# TT7-F_v1_4.net
KiCad netlist of a schematic drawn in EAGLE
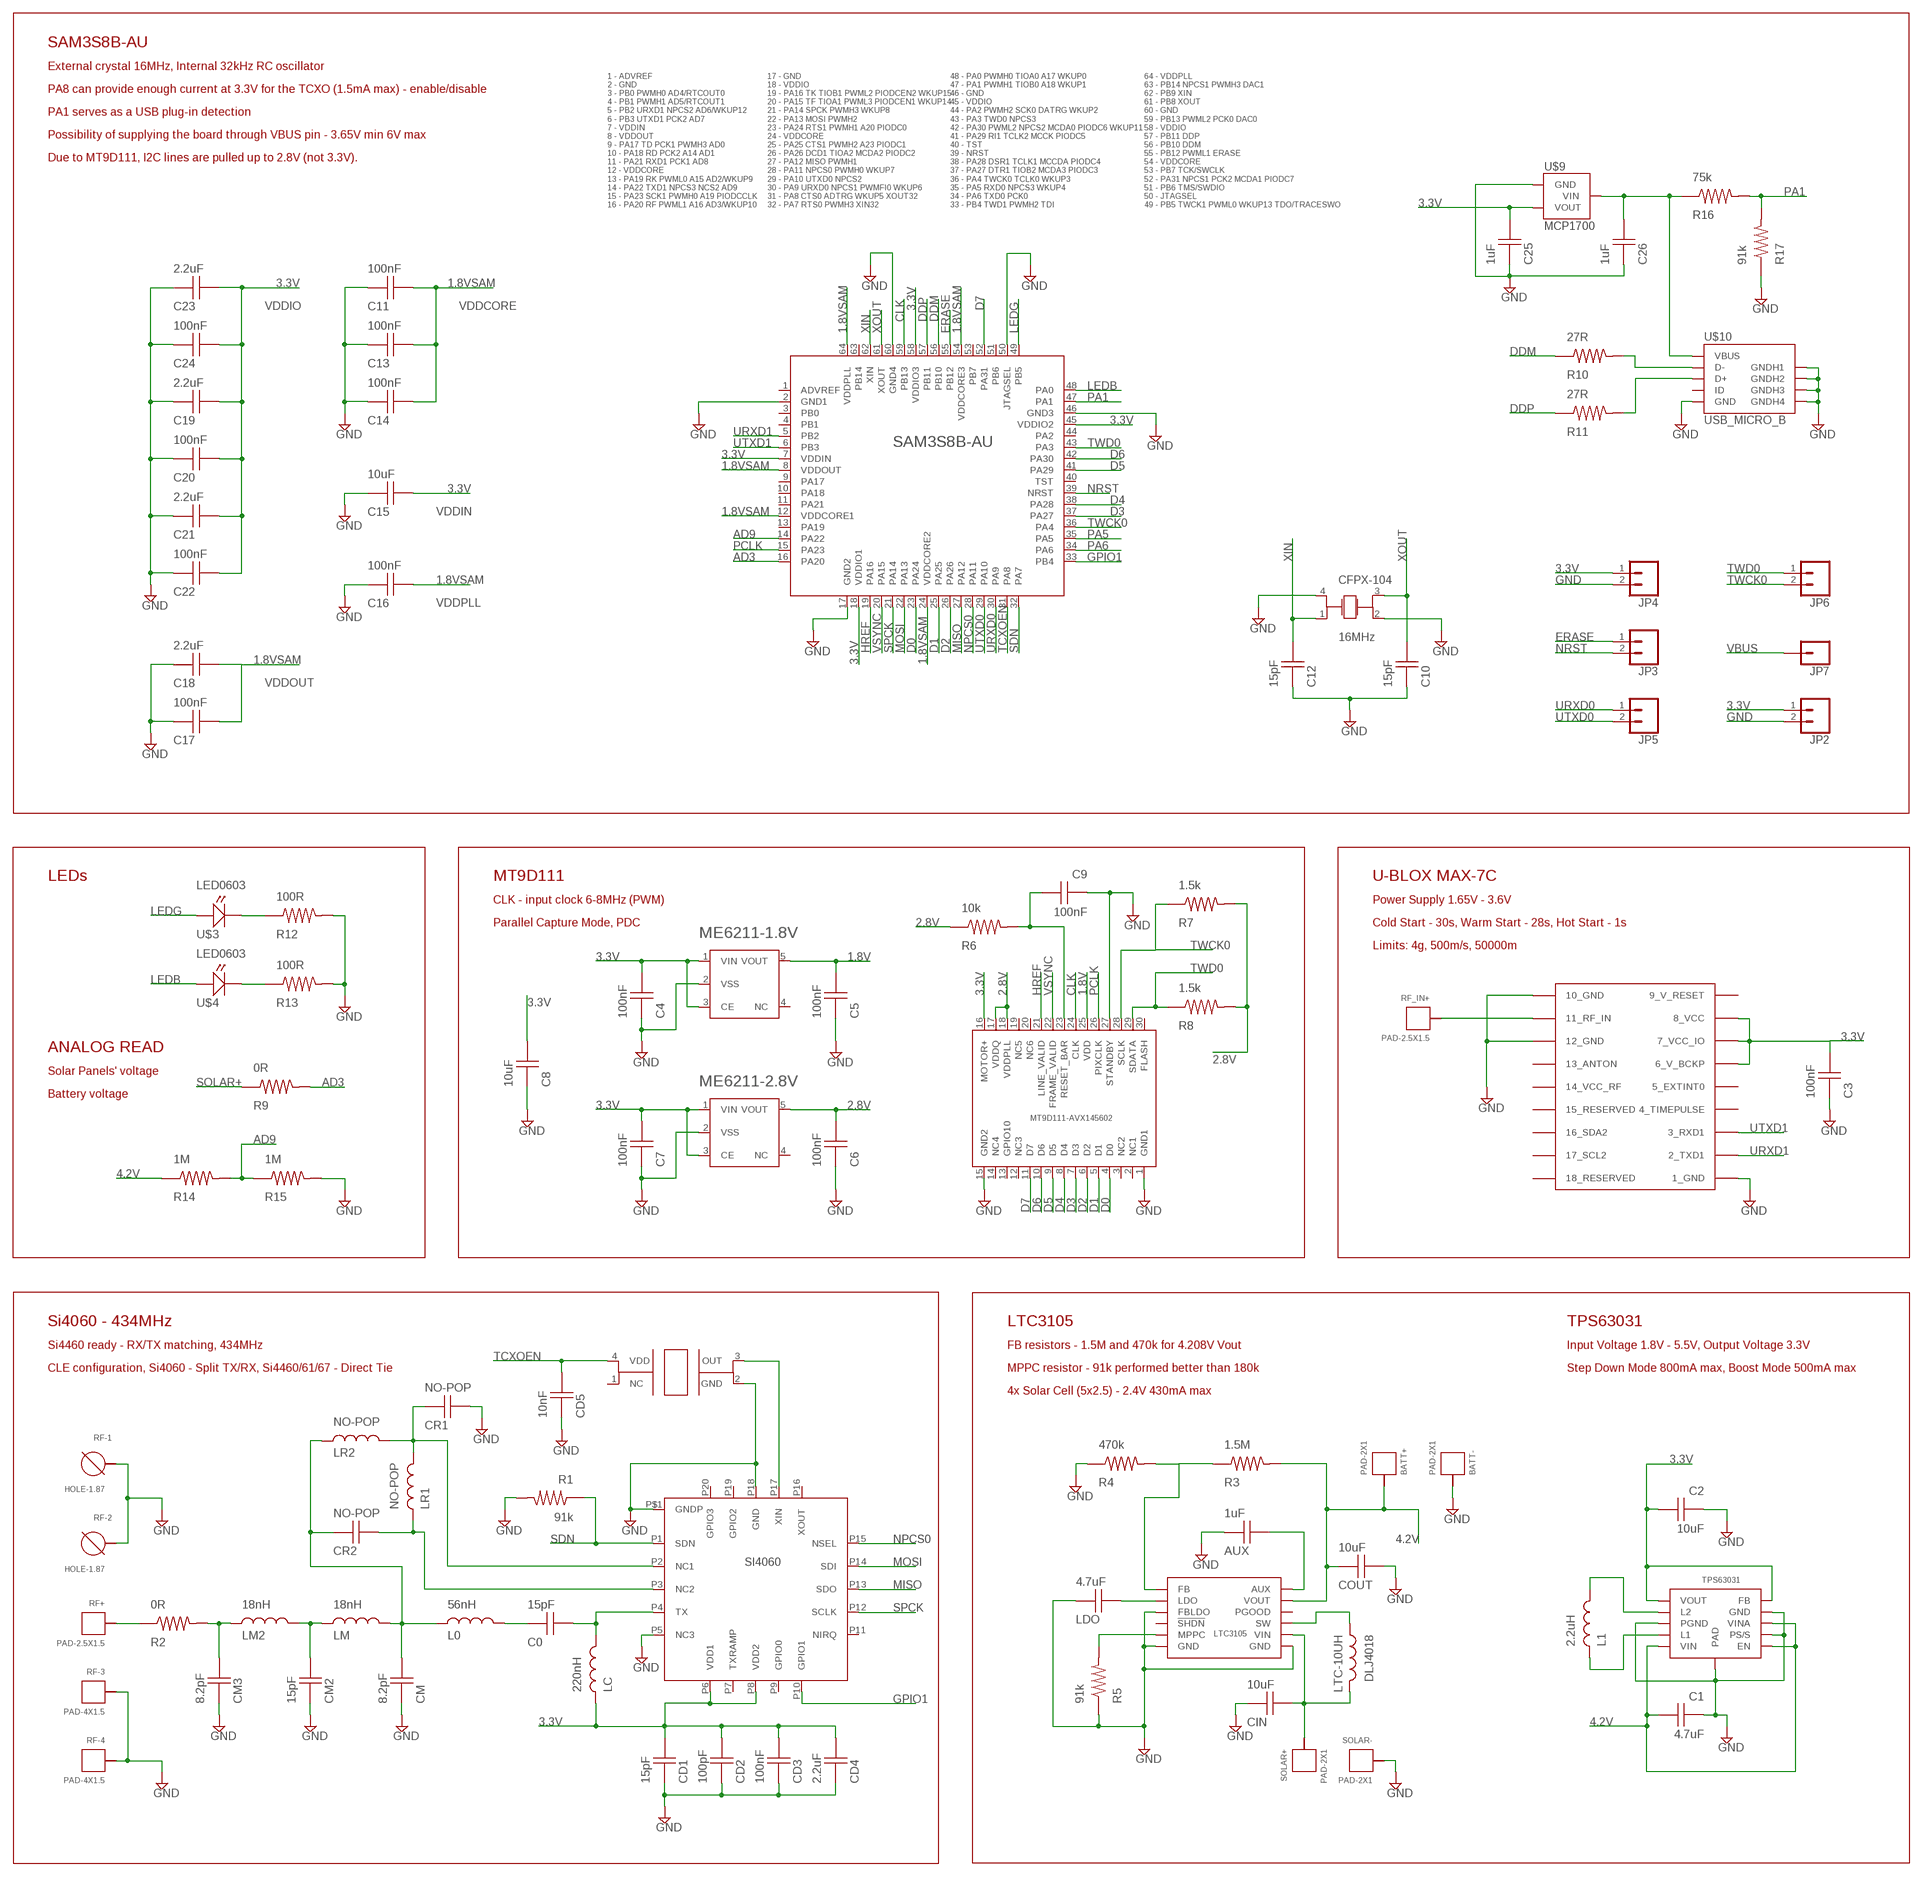
[diagram p0: schematic, sheet 1]

(export (version "E")
  (design (tool "Eeschema 10.0.6"))
  (components
    (comp (ref "AUX")
      (value "1uF")
      (footprint "eagle-import:CAP0603")
      (libsource (lib "eagle-import") (part "CAP0603"))
    )
    (comp (ref "BATT+")
      (value "PAD-2X1")
      (footprint "eagle-import:PAD-2X1")
      (libsource (lib "eagle-import") (part "PAD-2X1"))
    )
    (comp (ref "BATT-")
      (value "PAD-2X1")
      (footprint "eagle-import:PAD-2X1")
      (libsource (lib "eagle-import") (part "PAD-2X1"))
    )
    (comp (ref "C0")
      (value "15pF")
      (footprint "eagle-import:CAP0402")
      (libsource (lib "eagle-import") (part "CAP0402"))
    )
    (comp (ref "C1")
      (value "4.7uF")
      (footprint "eagle-import:CAP0603")
      (libsource (lib "eagle-import") (part "CAP0603"))
    )
    (comp (ref "C2")
      (value "10uF")
      (footprint "eagle-import:CAP0805")
      (libsource (lib "eagle-import") (part "CAP0805"))
    )
    (comp (ref "C3")
      (value "100nF")
      (footprint "eagle-import:CAP0402")
      (libsource (lib "eagle-import") (part "CAP0402"))
    )
    (comp (ref "C4")
      (value "100nF")
      (footprint "eagle-import:CAP0402")
      (libsource (lib "eagle-import") (part "CAP0402"))
    )
    (comp (ref "C5")
      (value "100nF")
      (footprint "eagle-import:CAP0402")
      (libsource (lib "eagle-import") (part "CAP0402"))
    )
    (comp (ref "C6")
      (value "100nF")
      (footprint "eagle-import:CAP0402")
      (libsource (lib "eagle-import") (part "CAP0402"))
    )
    (comp (ref "C7")
      (value "100nF")
      (footprint "eagle-import:CAP0402")
      (libsource (lib "eagle-import") (part "CAP0402"))
    )
    (comp (ref "C8")
      (value "10uF")
      (footprint "eagle-import:CAP0805")
      (libsource (lib "eagle-import") (part "CAP0805"))
    )
    (comp (ref "C9")
      (value "100nF")
      (footprint "eagle-import:CAP0402")
      (libsource (lib "eagle-import") (part "CAP0402"))
    )
    (comp (ref "C10")
      (value "15pF")
      (footprint "eagle-import:CAP0402")
      (libsource (lib "eagle-import") (part "CAP0402"))
    )
    (comp (ref "C11")
      (value "100nF")
      (footprint "eagle-import:CAP0402")
      (libsource (lib "eagle-import") (part "CAP0402"))
    )
    (comp (ref "C12")
      (value "15pF")
      (footprint "eagle-import:CAP0402")
      (libsource (lib "eagle-import") (part "CAP0402"))
    )
    (comp (ref "C13")
      (value "100nF")
      (footprint "eagle-import:CAP0402")
      (libsource (lib "eagle-import") (part "CAP0402"))
    )
    (comp (ref "C14")
      (value "100nF")
      (footprint "eagle-import:CAP0402")
      (libsource (lib "eagle-import") (part "CAP0402"))
    )
    (comp (ref "C15")
      (value "10uF")
      (footprint "eagle-import:CAP0603")
      (libsource (lib "eagle-import") (part "CAP0603"))
    )
    (comp (ref "C16")
      (value "100nF")
      (footprint "eagle-import:CAP0402")
      (libsource (lib "eagle-import") (part "CAP0402"))
    )
    (comp (ref "C17")
      (value "100nF")
      (footprint "eagle-import:CAP0402")
      (libsource (lib "eagle-import") (part "CAP0402"))
    )
    (comp (ref "C18")
      (value "2.2uF")
      (footprint "eagle-import:CAP0402")
      (libsource (lib "eagle-import") (part "CAP0402"))
    )
    (comp (ref "C19")
      (value "2.2uF")
      (footprint "eagle-import:CAP0402")
      (libsource (lib "eagle-import") (part "CAP0402"))
    )
    (comp (ref "C20")
      (value "100nF")
      (footprint "eagle-import:CAP0402")
      (libsource (lib "eagle-import") (part "CAP0402"))
    )
    (comp (ref "C21")
      (value "2.2uF")
      (footprint "eagle-import:CAP0402")
      (libsource (lib "eagle-import") (part "CAP0402"))
    )
    (comp (ref "C22")
      (value "100nF")
      (footprint "eagle-import:CAP0402")
      (libsource (lib "eagle-import") (part "CAP0402"))
    )
    (comp (ref "C23")
      (value "2.2uF")
      (footprint "eagle-import:CAP0402")
      (libsource (lib "eagle-import") (part "CAP0402"))
    )
    (comp (ref "C24")
      (value "100nF")
      (footprint "eagle-import:CAP0402")
      (libsource (lib "eagle-import") (part "CAP0402"))
    )
    (comp (ref "C25")
      (value "1uF")
      (footprint "eagle-import:CAP0603")
      (libsource (lib "eagle-import") (part "CAP0603"))
    )
    (comp (ref "C26")
      (value "1uF")
      (footprint "eagle-import:CAP0603")
      (libsource (lib "eagle-import") (part "CAP0603"))
    )
    (comp (ref "CD1")
      (value "15pF")
      (footprint "eagle-import:CAP0402")
      (libsource (lib "eagle-import") (part "CAP0402"))
    )
    (comp (ref "CD2")
      (value "100pF")
      (footprint "eagle-import:CAP0402")
      (libsource (lib "eagle-import") (part "CAP0402"))
    )
    (comp (ref "CD3")
      (value "100nF")
      (footprint "eagle-import:CAP0402")
      (libsource (lib "eagle-import") (part "CAP0402"))
    )
    (comp (ref "CD4")
      (value "2.2uF")
      (footprint "eagle-import:CAP0402")
      (libsource (lib "eagle-import") (part "CAP0402"))
    )
    (comp (ref "CD5")
      (value "10nF")
      (footprint "eagle-import:CAP0402")
      (libsource (lib "eagle-import") (part "CAP0402"))
    )
    (comp (ref "CFPX-104")
      (value "16MHz")
      (footprint "eagle-import:CFPX-104")
      (libsource (lib "eagle-import") (part "CFPX-104"))
    )
    (comp (ref "CIN")
      (value "10uF")
      (footprint "eagle-import:CAP0805")
      (libsource (lib "eagle-import") (part "CAP0805"))
    )
    (comp (ref "CM")
      (value "8.2pF")
      (footprint "eagle-import:CAP0402")
      (libsource (lib "eagle-import") (part "CAP0402"))
    )
    (comp (ref "CM2")
      (value "15pF")
      (footprint "eagle-import:CAP0402")
      (libsource (lib "eagle-import") (part "CAP0402"))
    )
    (comp (ref "CM3")
      (value "8.2pF")
      (footprint "eagle-import:CAP0402")
      (libsource (lib "eagle-import") (part "CAP0402"))
    )
    (comp (ref "COUT")
      (value "10uF")
      (footprint "eagle-import:CAP0805")
      (libsource (lib "eagle-import") (part "CAP0805"))
    )
    (comp (ref "CR1")
      (value "NO-POP")
      (footprint "eagle-import:CAP0402")
      (libsource (lib "eagle-import") (part "CAP0402"))
    )
    (comp (ref "CR2")
      (value "NO-POP")
      (footprint "eagle-import:CAP0402")
      (libsource (lib "eagle-import") (part "CAP0402"))
    )
    (comp (ref "JP2")
      (value "M021X02_NO_SILK")
      (footprint "eagle-import:1X02_NO_SILK")
      (libsource (lib "eagle-import") (part "M021X02_NO_SILK"))
    )
    (comp (ref "JP3")
      (value "M021X02_NO_SILK")
      (footprint "eagle-import:1X02_NO_SILK")
      (libsource (lib "eagle-import") (part "M021X02_NO_SILK"))
    )
    (comp (ref "JP4")
      (value "M021X02_NO_SILK")
      (footprint "eagle-import:1X02_NO_SILK")
      (libsource (lib "eagle-import") (part "M021X02_NO_SILK"))
    )
    (comp (ref "JP5")
      (value "M021X02_NO_SILK")
      (footprint "eagle-import:1X02_NO_SILK")
      (libsource (lib "eagle-import") (part "M021X02_NO_SILK"))
    )
    (comp (ref "JP6")
      (value "M021X02_NO_SILK")
      (footprint "eagle-import:1X02_NO_SILK")
      (libsource (lib "eagle-import") (part "M021X02_NO_SILK"))
    )
    (comp (ref "JP7")
      (value "M01PTH_NO_SILK_YES_STOP")
      (footprint "eagle-import:1X01_NO_SILK")
      (libsource (lib "eagle-import") (part "M01PTH_NO_SILK_YES_STOP"))
    )
    (comp (ref "L0")
      (value "56nH")
      (footprint "eagle-import:IND0402")
      (libsource (lib "eagle-import") (part "IND0402"))
    )
    (comp (ref "L1")
      (value "2.2uH")
      (footprint "eagle-import:DLJ3015")
      (libsource (lib "eagle-import") (part "DLJ3015"))
    )
    (comp (ref "LC")
      (value "220nH")
      (footprint "eagle-import:IND0402")
      (libsource (lib "eagle-import") (part "IND0402"))
    )
    (comp (ref "LDO")
      (value "4.7uF")
      (footprint "eagle-import:CAP0603")
      (libsource (lib "eagle-import") (part "CAP0603"))
    )
    (comp (ref "LM")
      (value "18nH")
      (footprint "eagle-import:IND0402")
      (libsource (lib "eagle-import") (part "IND0402"))
    )
    (comp (ref "LM2")
      (value "18nH")
      (footprint "eagle-import:IND0402")
      (libsource (lib "eagle-import") (part "IND0402"))
    )
    (comp (ref "LR1")
      (value "NO-POP")
      (footprint "eagle-import:IND0402")
      (libsource (lib "eagle-import") (part "IND0402"))
    )
    (comp (ref "LR2")
      (value "NO-POP")
      (footprint "eagle-import:IND0402")
      (libsource (lib "eagle-import") (part "IND0402"))
    )
    (comp (ref "LTC-10UH")
      (value "DLJ4018")
      (footprint "eagle-import:DLJ4018")
      (libsource (lib "eagle-import") (part "DLJ4018"))
    )
    (comp (ref "ME6211-1.8V")
      (value "ME6211")
      (footprint "eagle-import:ME6211")
      (libsource (lib "eagle-import") (part "ME6211"))
    )
    (comp (ref "ME6211-2.8V")
      (value "ME6211")
      (footprint "eagle-import:ME6211")
      (libsource (lib "eagle-import") (part "ME6211"))
    )
    (comp (ref "R1")
      (value "91k")
      (footprint "eagle-import:RES0402")
      (libsource (lib "eagle-import") (part "RES0402"))
    )
    (comp (ref "R2")
      (value "0R")
      (footprint "eagle-import:RES0402")
      (libsource (lib "eagle-import") (part "RES0402"))
    )
    (comp (ref "R3")
      (value "1.5M")
      (footprint "eagle-import:RES0402")
      (libsource (lib "eagle-import") (part "RES0402"))
    )
    (comp (ref "R4")
      (value "470k")
      (footprint "eagle-import:RES0402")
      (libsource (lib "eagle-import") (part "RES0402"))
    )
    (comp (ref "R5")
      (value "91k")
      (footprint "eagle-import:RES0402")
      (libsource (lib "eagle-import") (part "RES0402"))
    )
    (comp (ref "R6")
      (value "10k")
      (footprint "eagle-import:RES0402")
      (libsource (lib "eagle-import") (part "RES0402"))
    )
    (comp (ref "R7")
      (value "1.5k")
      (footprint "eagle-import:RES0402")
      (libsource (lib "eagle-import") (part "RES0402"))
    )
    (comp (ref "R8")
      (value "1.5k")
      (footprint "eagle-import:RES0402")
      (libsource (lib "eagle-import") (part "RES0402"))
    )
    (comp (ref "R9")
      (value "0R")
      (footprint "eagle-import:RES0402")
      (libsource (lib "eagle-import") (part "RES0402"))
    )
    (comp (ref "R10")
      (value "27R")
      (footprint "eagle-import:RES0402")
      (libsource (lib "eagle-import") (part "RES0402"))
    )
    (comp (ref "R11")
      (value "27R")
      (footprint "eagle-import:RES0402")
      (libsource (lib "eagle-import") (part "RES0402"))
    )
    (comp (ref "R12")
      (value "100R")
      (footprint "eagle-import:RES0402")
      (libsource (lib "eagle-import") (part "RES0402"))
    )
    (comp (ref "R13")
      (value "100R")
      (footprint "eagle-import:RES0402")
      (libsource (lib "eagle-import") (part "RES0402"))
    )
    (comp (ref "R14")
      (value "1M")
      (footprint "eagle-import:RES0603")
      (libsource (lib "eagle-import") (part "RES0603"))
    )
    (comp (ref "R15")
      (value "1M")
      (footprint "eagle-import:RES0603")
      (libsource (lib "eagle-import") (part "RES0603"))
    )
    (comp (ref "R16")
      (value "75k")
      (footprint "eagle-import:RES0402")
      (libsource (lib "eagle-import") (part "RES0402"))
    )
    (comp (ref "R17")
      (value "91k")
      (footprint "eagle-import:RES0402")
      (libsource (lib "eagle-import") (part "RES0402"))
    )
    (comp (ref "RF+")
      (value "PAD-2.5X1.5")
      (footprint "eagle-import:PAD-2.5X1.5")
      (libsource (lib "eagle-import") (part "PAD-2.5X1.5"))
    )
    (comp (ref "RF-1")
      (value "HOLE-1.87")
      (footprint "eagle-import:HOLE-1.87")
      (libsource (lib "eagle-import") (part "HOLE-1.87"))
    )
    (comp (ref "RF-2")
      (value "HOLE-1.87")
      (footprint "eagle-import:HOLE-1.87")
      (libsource (lib "eagle-import") (part "HOLE-1.87"))
    )
    (comp (ref "RF-3")
      (value "PAD-4X1.5")
      (footprint "eagle-import:PAD-4X1.5")
      (libsource (lib "eagle-import") (part "PAD-4X1.5"))
    )
    (comp (ref "RF-4")
      (value "PAD-4X1.5")
      (footprint "eagle-import:PAD-4X1.5")
      (libsource (lib "eagle-import") (part "PAD-4X1.5"))
    )
    (comp (ref "RF_IN+")
      (value "PAD-2.5X1.5")
      (footprint "eagle-import:PAD-2.5X1.5")
      (libsource (lib "eagle-import") (part "PAD-2.5X1.5"))
    )
    (comp (ref "SOLAR+")
      (value "PAD-2X1")
      (footprint "eagle-import:PAD-2X1")
      (libsource (lib "eagle-import") (part "PAD-2X1"))
    )
    (comp (ref "SOLAR-")
      (value "PAD-2X1")
      (footprint "eagle-import:PAD-2X1")
      (libsource (lib "eagle-import") (part "PAD-2X1"))
    )
    (comp (ref "TCXO")
      (value "32MHz")
      (footprint "eagle-import:I547-2P3_TCXO")
      (libsource (lib "eagle-import") (part "I547-2P3_TCXO"))
    )
    (comp (ref "U$1")
      (value "SI4060")
      (footprint "eagle-import:SI4060")
      (libsource (lib "eagle-import") (part "SI4060"))
    )
    (comp (ref "U$2")
      (value "UBLOX_MAX-7C")
      (footprint "eagle-import:UBLOX_MAX-7C")
      (libsource (lib "eagle-import") (part "UBLOX_MAX-7C"))
    )
    (comp (ref "U$3")
      (value "LED0603")
      (footprint "eagle-import:LED0603")
      (libsource (lib "eagle-import") (part "LED0603"))
    )
    (comp (ref "U$4")
      (value "LED0603")
      (footprint "eagle-import:LED0603")
      (libsource (lib "eagle-import") (part "LED0603"))
    )
    (comp (ref "U$9")
      (value "MCP1700")
      (footprint "eagle-import:MCP1700")
      (libsource (lib "eagle-import") (part "MCP1700"))
    )
    (comp (ref "U$10")
      (value "USB_MICRO_B")
      (footprint "eagle-import:USB_MICRO_B")
      (libsource (lib "eagle-import") (part "USB_MICRO_B"))
    )
    (comp (ref "U1")
      (value "LTC3105")
      (footprint "eagle-import:LTC3105")
      (libsource (lib "eagle-import") (part "LTC3105"))
    )
    (comp (ref "U2")
      (value "TPS63031")
      (footprint "eagle-import:TPS63031")
      (libsource (lib "eagle-import") (part "TPS63031"))
    )
    (comp (ref "U3")
      (value "MT9D111-AVX145602")
      (footprint "eagle-import:MT9D111-AVX145602")
      (libsource (lib "eagle-import") (part "MT9D111-AVX145602"))
    )
    (comp (ref "U4")
      (value "SAM3S8B-AU")
      (footprint "eagle-import:SAM3S8B-AU")
      (libsource (lib "eagle-import") (part "SAM3S8B-AU"))
    )
  )
  (nets
    (net (code "1") (name "/1.8V") (class "Default")
      (node (ref "C5") (pin "P$2") (pinfunction "P$2_P$2") (pintype "bidirectional"))
      (node (ref "ME6211-1.8V") (pin "5") (pinfunction "VOUT_5") (pintype "bidirectional"))
      (node (ref "U3") (pin "25") (pinfunction "VDD_25") (pintype "bidirectional"))
    )
    (net (code "2") (name "/1.8VSAM") (class "Default")
      (node (ref "C11") (pin "P$2") (pinfunction "P$2_P$2") (pintype "bidirectional"))
      (node (ref "C13") (pin "P$2") (pinfunction "P$2_P$2") (pintype "bidirectional"))
      (node (ref "C14") (pin "P$2") (pinfunction "P$2_P$2") (pintype "bidirectional"))
      (node (ref "C16") (pin "P$2") (pinfunction "P$2_P$2") (pintype "bidirectional"))
      (node (ref "C17") (pin "P$2") (pinfunction "P$2_P$2") (pintype "bidirectional"))
      (node (ref "C18") (pin "P$2") (pinfunction "P$2_P$2") (pintype "bidirectional"))
      (node (ref "U4") (pin "12") (pinfunction "VDDCORE1_12") (pintype "bidirectional"))
      (node (ref "U4") (pin "24") (pinfunction "VDDCORE2_24") (pintype "bidirectional"))
      (node (ref "U4") (pin "54") (pinfunction "VDDCORE3_54") (pintype "bidirectional"))
      (node (ref "U4") (pin "64") (pinfunction "VDDPLL_64") (pintype "bidirectional"))
      (node (ref "U4") (pin "8") (pinfunction "VDDOUT_8") (pintype "bidirectional"))
    )
    (net (code "3") (name "/2.8V") (class "Default")
      (node (ref "C6") (pin "P$2") (pinfunction "P$2_P$2") (pintype "bidirectional"))
      (node (ref "ME6211-2.8V") (pin "5") (pinfunction "VOUT_5") (pintype "bidirectional"))
      (node (ref "R6") (pin "P$1") (pinfunction "P$1_P$1") (pintype "bidirectional"))
      (node (ref "R7") (pin "P$2") (pinfunction "P$2_P$2") (pintype "bidirectional"))
      (node (ref "R8") (pin "P$2") (pinfunction "P$2_P$2") (pintype "bidirectional"))
      (node (ref "U3") (pin "17") (pinfunction "VDDQ_17") (pintype "bidirectional"))
      (node (ref "U3") (pin "18") (pinfunction "VDDPLL_18") (pintype "bidirectional"))
    )
    (net (code "4") (name "/3.3V") (class "Default")
      (node (ref "C15") (pin "P$2") (pinfunction "P$2_P$2") (pintype "bidirectional"))
      (node (ref "C19") (pin "P$2") (pinfunction "P$2_P$2") (pintype "bidirectional"))
      (node (ref "C2") (pin "P$2") (pinfunction "P$2_P$2") (pintype "bidirectional"))
      (node (ref "C20") (pin "P$2") (pinfunction "P$2_P$2") (pintype "bidirectional"))
      (node (ref "C21") (pin "P$2") (pinfunction "P$2_P$2") (pintype "bidirectional"))
      (node (ref "C22") (pin "P$2") (pinfunction "P$2_P$2") (pintype "bidirectional"))
      (node (ref "C23") (pin "P$2") (pinfunction "P$2_P$2") (pintype "bidirectional"))
      (node (ref "C24") (pin "P$2") (pinfunction "P$2_P$2") (pintype "bidirectional"))
      (node (ref "C25") (pin "P$2") (pinfunction "P$2_P$2") (pintype "bidirectional"))
      (node (ref "C3") (pin "P$2") (pinfunction "P$2_P$2") (pintype "bidirectional"))
      (node (ref "C4") (pin "P$2") (pinfunction "P$2_P$2") (pintype "bidirectional"))
      (node (ref "C7") (pin "P$2") (pinfunction "P$2_P$2") (pintype "bidirectional"))
      (node (ref "C8") (pin "P$2") (pinfunction "P$2_P$2") (pintype "bidirectional"))
      (node (ref "CD1") (pin "P$2") (pinfunction "P$2_P$2") (pintype "bidirectional"))
      (node (ref "CD2") (pin "P$2") (pinfunction "P$2_P$2") (pintype "bidirectional"))
      (node (ref "CD3") (pin "P$2") (pinfunction "P$2_P$2") (pintype "bidirectional"))
      (node (ref "CD4") (pin "P$2") (pinfunction "P$2_P$2") (pintype "bidirectional"))
      (node (ref "JP2") (pin "1") (pinfunction "1_1") (pintype "passive"))
      (node (ref "JP4") (pin "1") (pinfunction "1_1") (pintype "passive"))
      (node (ref "LC") (pin "P$1") (pinfunction "P$1_P$1") (pintype "bidirectional"))
      (node (ref "ME6211-1.8V") (pin "1") (pinfunction "VIN_1") (pintype "bidirectional"))
      (node (ref "ME6211-1.8V") (pin "3") (pinfunction "CE_3") (pintype "bidirectional"))
      (node (ref "ME6211-2.8V") (pin "1") (pinfunction "VIN_1") (pintype "bidirectional"))
      (node (ref "ME6211-2.8V") (pin "3") (pinfunction "CE_3") (pintype "bidirectional"))
      (node (ref "U$1") (pin "P6") (pinfunction "VDD1_P6") (pintype "bidirectional"))
      (node (ref "U$1") (pin "P8") (pinfunction "VDD2_P8") (pintype "bidirectional"))
      (node (ref "U$2") (pin "6_V_BCKP") (pinfunction "6_V_BCKP_6_V_BCKP") (pintype "bidirectional"))
      (node (ref "U$2") (pin "7_VCC_IO") (pinfunction "7_VCC_IO_7_VCC_IO") (pintype "power_in"))
      (node (ref "U$2") (pin "8_VCC") (pinfunction "8_VCC_8_VCC") (pintype "power_in"))
      (node (ref "U$9") (pin "2") (pinfunction "VOUT_2") (pintype "bidirectional"))
      (node (ref "U2") (pin "1") (pinfunction "VOUT_1") (pintype "bidirectional"))
      (node (ref "U2") (pin "10") (pinfunction "FB_10") (pintype "bidirectional"))
      (node (ref "U3") (pin "16") (pinfunction "MOTOR+_16") (pintype "bidirectional"))
      (node (ref "U4") (pin "18") (pinfunction "VDDIO1_18") (pintype "bidirectional"))
      (node (ref "U4") (pin "45") (pinfunction "VDDIO2_45") (pintype "bidirectional"))
      (node (ref "U4") (pin "58") (pinfunction "VDDIO3_58") (pintype "bidirectional"))
      (node (ref "U4") (pin "7") (pinfunction "VDDIN_7") (pintype "bidirectional"))
    )
    (net (code "5") (name "/4.2V") (class "Default")
      (node (ref "BATT+") (pin "P$1") (pinfunction "P$1_P$1") (pintype "bidirectional"))
      (node (ref "C1") (pin "P$2") (pinfunction "P$2_P$2") (pintype "bidirectional"))
      (node (ref "COUT") (pin "P$1") (pinfunction "P$1_P$1") (pintype "bidirectional"))
      (node (ref "R14") (pin "P$1") (pinfunction "P$1_P$1") (pintype "bidirectional"))
      (node (ref "R3") (pin "P$2") (pinfunction "P$2_P$2") (pintype "bidirectional"))
      (node (ref "U1") (pin "11") (pinfunction "VOUT_11") (pintype "bidirectional"))
      (node (ref "U2") (pin "5") (pinfunction "VIN_5") (pintype "bidirectional"))
      (node (ref "U2") (pin "6") (pinfunction "EN_6") (pintype "bidirectional"))
      (node (ref "U2") (pin "8") (pinfunction "VINA_8") (pintype "bidirectional"))
    )
    (net (code "6") (name "/9_V_RESET") (class "Default")
      (node (ref "U$2") (pin "9_V_RESET") (pinfunction "9_V_RESET_9_V_RESET") (pintype "power_in"))
    )
    (net (code "7") (name "/AD3") (class "Default")
      (node (ref "R9") (pin "P$2") (pinfunction "P$2_P$2") (pintype "bidirectional"))
      (node (ref "U4") (pin "16") (pinfunction "PA20_16") (pintype "bidirectional"))
    )
    (net (code "8") (name "/AD9") (class "Default")
      (node (ref "R14") (pin "P$2") (pinfunction "P$2_P$2") (pintype "bidirectional"))
      (node (ref "R15") (pin "P$1") (pinfunction "P$1_P$1") (pintype "bidirectional"))
      (node (ref "U4") (pin "14") (pinfunction "PA22_14") (pintype "bidirectional"))
    )
    (net (code "9") (name "/CLK") (class "Default")
      (node (ref "U3") (pin "24") (pinfunction "CLK_24") (pintype "bidirectional"))
      (node (ref "U4") (pin "59") (pinfunction "PB13_59") (pintype "bidirectional"))
    )
    (net (code "10") (name "/D0") (class "Default")
      (node (ref "U3") (pin "4") (pinfunction "D0_4") (pintype "bidirectional"))
      (node (ref "U4") (pin "23") (pinfunction "PA24_23") (pintype "bidirectional"))
    )
    (net (code "11") (name "/D1") (class "Default")
      (node (ref "U3") (pin "5") (pinfunction "D1_5") (pintype "bidirectional"))
      (node (ref "U4") (pin "25") (pinfunction "PA25_25") (pintype "bidirectional"))
    )
    (net (code "12") (name "/D2") (class "Default")
      (node (ref "U3") (pin "6") (pinfunction "D2_6") (pintype "bidirectional"))
      (node (ref "U4") (pin "26") (pinfunction "PA26_26") (pintype "bidirectional"))
    )
    (net (code "13") (name "/D3") (class "Default")
      (node (ref "U3") (pin "7") (pinfunction "D3_7") (pintype "bidirectional"))
      (node (ref "U4") (pin "37") (pinfunction "PA27_37") (pintype "bidirectional"))
    )
    (net (code "14") (name "/D4") (class "Default")
      (node (ref "U3") (pin "8") (pinfunction "D4_8") (pintype "bidirectional"))
      (node (ref "U4") (pin "38") (pinfunction "PA28_38") (pintype "bidirectional"))
    )
    (net (code "15") (name "/D5") (class "Default")
      (node (ref "U3") (pin "9") (pinfunction "D5_9") (pintype "bidirectional"))
      (node (ref "U4") (pin "41") (pinfunction "PA29_41") (pintype "bidirectional"))
    )
    (net (code "16") (name "/D6") (class "Default")
      (node (ref "U3") (pin "10") (pinfunction "D6_10") (pintype "bidirectional"))
      (node (ref "U4") (pin "42") (pinfunction "PA30_42") (pintype "bidirectional"))
    )
    (net (code "17") (name "/D7") (class "Default")
      (node (ref "U3") (pin "11") (pinfunction "D7_11") (pintype "bidirectional"))
      (node (ref "U4") (pin "52") (pinfunction "PA31_52") (pintype "bidirectional"))
    )
    (net (code "18") (name "/DDM") (class "Default")
      (node (ref "R10") (pin "P$1") (pinfunction "P$1_P$1") (pintype "bidirectional"))
      (node (ref "U4") (pin "56") (pinfunction "PB10_56") (pintype "bidirectional"))
    )
    (net (code "19") (name "/DDP") (class "Default")
      (node (ref "R11") (pin "P$1") (pinfunction "P$1_P$1") (pintype "bidirectional"))
      (node (ref "U4") (pin "57") (pinfunction "PB11_57") (pintype "bidirectional"))
    )
    (net (code "20") (name "/ERASE") (class "Default")
      (node (ref "JP3") (pin "1") (pinfunction "1_1") (pintype "passive"))
      (node (ref "U4") (pin "55") (pinfunction "PB12_55") (pintype "bidirectional"))
    )
    (net (code "21") (name "/GPIO1") (class "Default")
      (node (ref "U$1") (pin "P10") (pinfunction "GPIO1_P10") (pintype "bidirectional"))
      (node (ref "U4") (pin "33") (pinfunction "PB4_33") (pintype "bidirectional"))
    )
    (net (code "22") (name "/HREF") (class "Default")
      (node (ref "U3") (pin "21") (pinfunction "LINE_VALID_21") (pintype "bidirectional"))
      (node (ref "U4") (pin "19") (pinfunction "PA16_19") (pintype "bidirectional"))
    )
    (net (code "23") (name "/LEDB") (class "Default")
      (node (ref "U$4") (pin "ANODE") (pinfunction "ANODE_ANODE") (pintype "bidirectional"))
      (node (ref "U4") (pin "48") (pinfunction "PA0_48") (pintype "bidirectional"))
    )
    (net (code "24") (name "/LEDG") (class "Default")
      (node (ref "U$3") (pin "ANODE") (pinfunction "ANODE_ANODE") (pintype "bidirectional"))
      (node (ref "U4") (pin "49") (pinfunction "PB5_49") (pintype "bidirectional"))
    )
    (net (code "25") (name "/MISO") (class "Default")
      (node (ref "U$1") (pin "P13") (pinfunction "SDO_P13") (pintype "bidirectional"))
      (node (ref "U4") (pin "27") (pinfunction "PA12_27") (pintype "bidirectional"))
    )
    (net (code "26") (name "/MOSI") (class "Default")
      (node (ref "U$1") (pin "P14") (pinfunction "SDI_P14") (pintype "bidirectional"))
      (node (ref "U4") (pin "22") (pinfunction "PA13_22") (pintype "bidirectional"))
    )
    (net (code "27") (name "/NPCS0") (class "Default")
      (node (ref "U$1") (pin "P15") (pinfunction "NSEL_P15") (pintype "bidirectional"))
      (node (ref "U4") (pin "28") (pinfunction "PA11_28") (pintype "bidirectional"))
    )
    (net (code "28") (name "/NRST") (class "Default")
      (node (ref "JP3") (pin "2") (pinfunction "2_2") (pintype "passive"))
      (node (ref "U4") (pin "39") (pinfunction "NRST_39") (pintype "bidirectional"))
    )
    (net (code "29") (name "/PA1") (class "Default")
      (node (ref "R16") (pin "P$2") (pinfunction "P$2_P$2") (pintype "bidirectional"))
      (node (ref "R17") (pin "P$2") (pinfunction "P$2_P$2") (pintype "bidirectional"))
      (node (ref "U4") (pin "47") (pinfunction "PA1_47") (pintype "bidirectional"))
    )
    (net (code "30") (name "/PA5") (class "Default")
      (node (ref "U4") (pin "35") (pinfunction "PA5_35") (pintype "bidirectional"))
    )
    (net (code "31") (name "/PA6") (class "Default")
      (node (ref "U4") (pin "34") (pinfunction "PA6_34") (pintype "bidirectional"))
    )
    (net (code "32") (name "/PCLK") (class "Default")
      (node (ref "U3") (pin "26") (pinfunction "PIXCLK_26") (pintype "bidirectional"))
      (node (ref "U4") (pin "15") (pinfunction "PA23_15") (pintype "bidirectional"))
    )
    (net (code "33") (name "/SDN") (class "Default")
      (node (ref "R1") (pin "P$1") (pinfunction "P$1_P$1") (pintype "bidirectional"))
      (node (ref "U$1") (pin "P1") (pinfunction "SDN_P1") (pintype "bidirectional"))
      (node (ref "U4") (pin "32") (pinfunction "PA7_32") (pintype "bidirectional"))
    )
    (net (code "34") (name "/SOLAR+") (class "Default")
      (node (ref "CIN") (pin "P$2") (pinfunction "P$2_P$2") (pintype "bidirectional"))
      (node (ref "LTC-10UH") (pin "P$2") (pinfunction "P$2_P$2") (pintype "bidirectional"))
      (node (ref "R9") (pin "P$1") (pinfunction "P$1_P$1") (pintype "bidirectional"))
      (node (ref "SOLAR+") (pin "P$1") (pinfunction "P$1_P$1") (pintype "bidirectional"))
      (node (ref "U1") (pin "8") (pinfunction "VIN_8") (pintype "bidirectional"))
    )
    (net (code "35") (name "/SPCK") (class "Default")
      (node (ref "U$1") (pin "P12") (pinfunction "SCLK_P12") (pintype "bidirectional"))
      (node (ref "U4") (pin "21") (pinfunction "PA14_21") (pintype "bidirectional"))
    )
    (net (code "36") (name "/TCXOEN") (class "Default")
      (node (ref "CD5") (pin "P$2") (pinfunction "P$2_P$2") (pintype "bidirectional"))
      (node (ref "TCXO") (pin "4") (pinfunction "VDD_4") (pintype "bidirectional"))
      (node (ref "U4") (pin "31") (pinfunction "PA8_31") (pintype "bidirectional"))
    )
    (net (code "37") (name "/TWCK0") (class "Default")
      (node (ref "JP6") (pin "2") (pinfunction "2_2") (pintype "passive"))
      (node (ref "R7") (pin "P$1") (pinfunction "P$1_P$1") (pintype "bidirectional"))
      (node (ref "U3") (pin "28") (pinfunction "SCLK_28") (pintype "bidirectional"))
      (node (ref "U4") (pin "36") (pinfunction "PA4_36") (pintype "bidirectional"))
    )
    (net (code "38") (name "/TWD0") (class "Default")
      (node (ref "JP6") (pin "1") (pinfunction "1_1") (pintype "passive"))
      (node (ref "R8") (pin "P$1") (pinfunction "P$1_P$1") (pintype "bidirectional"))
      (node (ref "U3") (pin "29") (pinfunction "SDATA_29") (pintype "bidirectional"))
      (node (ref "U4") (pin "43") (pinfunction "PA3_43") (pintype "bidirectional"))
    )
    (net (code "39") (name "/URXD0") (class "Default")
      (node (ref "JP5") (pin "1") (pinfunction "1_1") (pintype "passive"))
      (node (ref "U4") (pin "30") (pinfunction "PA9_30") (pintype "bidirectional"))
    )
    (net (code "40") (name "/URXD1") (class "Default")
      (node (ref "U$2") (pin "2_TXD1") (pinfunction "2_TXD1_2_TXD1") (pintype "bidirectional"))
      (node (ref "U4") (pin "5") (pinfunction "PB2_5") (pintype "bidirectional"))
    )
    (net (code "41") (name "/UTXD0") (class "Default")
      (node (ref "JP5") (pin "2") (pinfunction "2_2") (pintype "passive"))
      (node (ref "U4") (pin "29") (pinfunction "PA10_29") (pintype "bidirectional"))
    )
    (net (code "42") (name "/UTXD1") (class "Default")
      (node (ref "U$2") (pin "3_RXD1") (pinfunction "3_RXD1_3_RXD1") (pintype "bidirectional"))
      (node (ref "U4") (pin "6") (pinfunction "PB3_6") (pintype "bidirectional"))
    )
    (net (code "43") (name "/VBUS") (class "Default")
      (node (ref "C26") (pin "P$2") (pinfunction "P$2_P$2") (pintype "bidirectional"))
      (node (ref "JP7") (pin "1") (pinfunction "1_1") (pintype "passive"))
      (node (ref "R16") (pin "P$1") (pinfunction "P$1_P$1") (pintype "bidirectional"))
      (node (ref "U$10") (pin "VBUS") (pinfunction "VBUS_VBUS") (pintype "bidirectional"))
      (node (ref "U$9") (pin "3") (pinfunction "VIN_3") (pintype "bidirectional"))
    )
    (net (code "44") (name "/VSYNC") (class "Default")
      (node (ref "U3") (pin "22") (pinfunction "FRAME_VALID_22") (pintype "bidirectional"))
      (node (ref "U4") (pin "20") (pinfunction "PA15_20") (pintype "bidirectional"))
    )
    (net (code "45") (name "/XIN") (class "Default")
      (node (ref "C12") (pin "P$2") (pinfunction "P$2_P$2") (pintype "bidirectional"))
      (node (ref "CFPX-104") (pin "1") (pinfunction "XTAL1_1") (pintype "bidirectional"))
      (node (ref "U4") (pin "62") (pinfunction "XIN_62") (pintype "bidirectional"))
    )
    (net (code "46") (name "/XOUT") (class "Default")
      (node (ref "C10") (pin "P$2") (pinfunction "P$2_P$2") (pintype "bidirectional"))
      (node (ref "CFPX-104") (pin "3") (pinfunction "XTAL2_3") (pintype "bidirectional"))
      (node (ref "U4") (pin "61") (pinfunction "XOUT_61") (pintype "bidirectional"))
    )
    (net (code "47") (name "GND") (class "Default")
      (node (ref "AUX") (pin "P$1") (pinfunction "P$1_P$1") (pintype "bidirectional"))
      (node (ref "BATT-") (pin "P$1") (pinfunction "P$1_P$1") (pintype "bidirectional"))
      (node (ref "C1") (pin "P$1") (pinfunction "P$1_P$1") (pintype "bidirectional"))
      (node (ref "C10") (pin "P$1") (pinfunction "P$1_P$1") (pintype "bidirectional"))
      (node (ref "C11") (pin "P$1") (pinfunction "P$1_P$1") (pintype "bidirectional"))
      (node (ref "C12") (pin "P$1") (pinfunction "P$1_P$1") (pintype "bidirectional"))
      (node (ref "C13") (pin "P$1") (pinfunction "P$1_P$1") (pintype "bidirectional"))
      (node (ref "C14") (pin "P$1") (pinfunction "P$1_P$1") (pintype "bidirectional"))
      (node (ref "C15") (pin "P$1") (pinfunction "P$1_P$1") (pintype "bidirectional"))
      (node (ref "C16") (pin "P$1") (pinfunction "P$1_P$1") (pintype "bidirectional"))
      (node (ref "C17") (pin "P$1") (pinfunction "P$1_P$1") (pintype "bidirectional"))
      (node (ref "C18") (pin "P$1") (pinfunction "P$1_P$1") (pintype "bidirectional"))
      (node (ref "C19") (pin "P$1") (pinfunction "P$1_P$1") (pintype "bidirectional"))
      (node (ref "C2") (pin "P$1") (pinfunction "P$1_P$1") (pintype "bidirectional"))
      (node (ref "C20") (pin "P$1") (pinfunction "P$1_P$1") (pintype "bidirectional"))
      (node (ref "C21") (pin "P$1") (pinfunction "P$1_P$1") (pintype "bidirectional"))
      (node (ref "C22") (pin "P$1") (pinfunction "P$1_P$1") (pintype "bidirectional"))
      (node (ref "C23") (pin "P$1") (pinfunction "P$1_P$1") (pintype "bidirectional"))
      (node (ref "C24") (pin "P$1") (pinfunction "P$1_P$1") (pintype "bidirectional"))
      (node (ref "C25") (pin "P$1") (pinfunction "P$1_P$1") (pintype "bidirectional"))
      (node (ref "C26") (pin "P$1") (pinfunction "P$1_P$1") (pintype "bidirectional"))
      (node (ref "C3") (pin "P$1") (pinfunction "P$1_P$1") (pintype "bidirectional"))
      (node (ref "C4") (pin "P$1") (pinfunction "P$1_P$1") (pintype "bidirectional"))
      (node (ref "C5") (pin "P$1") (pinfunction "P$1_P$1") (pintype "bidirectional"))
      (node (ref "C6") (pin "P$1") (pinfunction "P$1_P$1") (pintype "bidirectional"))
      (node (ref "C7") (pin "P$1") (pinfunction "P$1_P$1") (pintype "bidirectional"))
      (node (ref "C8") (pin "P$1") (pinfunction "P$1_P$1") (pintype "bidirectional"))
      (node (ref "C9") (pin "P$1") (pinfunction "P$1_P$1") (pintype "bidirectional"))
      (node (ref "CD1") (pin "P$1") (pinfunction "P$1_P$1") (pintype "bidirectional"))
      (node (ref "CD2") (pin "P$1") (pinfunction "P$1_P$1") (pintype "bidirectional"))
      (node (ref "CD3") (pin "P$1") (pinfunction "P$1_P$1") (pintype "bidirectional"))
      (node (ref "CD4") (pin "P$1") (pinfunction "P$1_P$1") (pintype "bidirectional"))
      (node (ref "CD5") (pin "P$1") (pinfunction "P$1_P$1") (pintype "bidirectional"))
      (node (ref "CFPX-104") (pin "2") (pinfunction "GND1_2") (pintype "bidirectional"))
      (node (ref "CFPX-104") (pin "4") (pinfunction "GND2_4") (pintype "bidirectional"))
      (node (ref "CIN") (pin "P$1") (pinfunction "P$1_P$1") (pintype "bidirectional"))
      (node (ref "CM") (pin "P$1") (pinfunction "P$1_P$1") (pintype "bidirectional"))
      (node (ref "CM2") (pin "P$1") (pinfunction "P$1_P$1") (pintype "bidirectional"))
      (node (ref "CM3") (pin "P$1") (pinfunction "P$1_P$1") (pintype "bidirectional"))
      (node (ref "COUT") (pin "P$2") (pinfunction "P$2_P$2") (pintype "bidirectional"))
      (node (ref "CR1") (pin "P$2") (pinfunction "P$2_P$2") (pintype "bidirectional"))
      (node (ref "JP2") (pin "2") (pinfunction "2_2") (pintype "passive"))
      (node (ref "JP4") (pin "2") (pinfunction "2_2") (pintype "passive"))
      (node (ref "LDO") (pin "P$1") (pinfunction "P$1_P$1") (pintype "bidirectional"))
      (node (ref "ME6211-1.8V") (pin "2") (pinfunction "VSS_2") (pintype "bidirectional"))
      (node (ref "ME6211-2.8V") (pin "2") (pinfunction "VSS_2") (pintype "bidirectional"))
      (node (ref "R1") (pin "P$2") (pinfunction "P$2_P$2") (pintype "bidirectional"))
      (node (ref "R12") (pin "P$2") (pinfunction "P$2_P$2") (pintype "bidirectional"))
      (node (ref "R13") (pin "P$2") (pinfunction "P$2_P$2") (pintype "bidirectional"))
      (node (ref "R15") (pin "P$2") (pinfunction "P$2_P$2") (pintype "bidirectional"))
      (node (ref "R17") (pin "P$1") (pinfunction "P$1_P$1") (pintype "bidirectional"))
      (node (ref "R4") (pin "P$1") (pinfunction "P$1_P$1") (pintype "bidirectional"))
      (node (ref "R5") (pin "P$1") (pinfunction "P$1_P$1") (pintype "bidirectional"))
      (node (ref "RF-1") (pin "P$1") (pinfunction "P$1_P$1") (pintype "bidirectional"))
      (node (ref "RF-2") (pin "P$1") (pinfunction "P$1_P$1") (pintype "bidirectional"))
      (node (ref "RF-3") (pin "P$1") (pinfunction "P$1_P$1") (pintype "bidirectional"))
      (node (ref "RF-4") (pin "P$1") (pinfunction "P$1_P$1") (pintype "bidirectional"))
      (node (ref "SOLAR-") (pin "P$1") (pinfunction "P$1_P$1") (pintype "bidirectional"))
      (node (ref "TCXO") (pin "2") (pinfunction "GND_2") (pintype "bidirectional"))
      (node (ref "U$1") (pin "P$1") (pinfunction "GNDP_P$1") (pintype "bidirectional"))
      (node (ref "U$1") (pin "P18") (pinfunction "GND_P18") (pintype "bidirectional"))
      (node (ref "U$1") (pin "P5") (pinfunction "NC3_P5") (pintype "bidirectional"))
      (node (ref "U$10") (pin "GND") (pinfunction "GND_GND") (pintype "bidirectional"))
      (node (ref "U$10") (pin "P$6") (pinfunction "GNDH1_P$6") (pintype "bidirectional"))
      (node (ref "U$10") (pin "P$7") (pinfunction "GNDH2_P$7") (pintype "bidirectional"))
      (node (ref "U$10") (pin "P$8") (pinfunction "GNDH3_P$8") (pintype "bidirectional"))
      (node (ref "U$10") (pin "P$9") (pinfunction "GNDH4_P$9") (pintype "bidirectional"))
      (node (ref "U$2") (pin "10_GND") (pinfunction "10_GND_10_GND") (pintype "power_in"))
      (node (ref "U$2") (pin "12_GND") (pinfunction "12_GND_12_GND") (pintype "power_in"))
      (node (ref "U$2") (pin "1_GND") (pinfunction "1_GND_1_GND") (pintype "power_in"))
      (node (ref "U$9") (pin "1") (pinfunction "GND_1") (pintype "bidirectional"))
      (node (ref "U1") (pin "3") (pinfunction "FBLDO_3") (pintype "bidirectional"))
      (node (ref "U1") (pin "6") (pinfunction "GND_6") (pintype "bidirectional"))
      (node (ref "U1") (pin "7") (pinfunction "GND_7") (pintype "bidirectional"))
      (node (ref "U2") (pin "11") (pinfunction "PAD_11") (pintype "bidirectional"))
      (node (ref "U2") (pin "3") (pinfunction "PGND_3") (pintype "bidirectional"))
      (node (ref "U2") (pin "7") (pinfunction "PS/S_7") (pintype "bidirectional"))
      (node (ref "U2") (pin "9") (pinfunction "GND_9") (pintype "bidirectional"))
      (node (ref "U3") (pin "1") (pinfunction "GND1_1") (pintype "bidirectional"))
      (node (ref "U3") (pin "15") (pinfunction "GND2_15") (pintype "bidirectional"))
      (node (ref "U3") (pin "27") (pinfunction "STANDBY_27") (pintype "bidirectional"))
      (node (ref "U4") (pin "17") (pinfunction "GND2_17") (pintype "bidirectional"))
      (node (ref "U4") (pin "2") (pinfunction "GND1_2") (pintype "bidirectional"))
      (node (ref "U4") (pin "46") (pinfunction "GND3_46") (pintype "bidirectional"))
      (node (ref "U4") (pin "50") (pinfunction "JTAGSEL_50") (pintype "bidirectional"))
      (node (ref "U4") (pin "60") (pinfunction "GND4_60") (pintype "bidirectional"))
    )
    (net (code "48") (name "Net-(C0-PadP$1)") (class "Default")
      (node (ref "C0") (pin "P$1") (pinfunction "P$1_P$1") (pintype "bidirectional"))
      (node (ref "L0") (pin "P$2") (pinfunction "P$2_P$2") (pintype "bidirectional"))
    )
    (net (code "49") (name "Net-(CM-PadP$2)") (class "Default")
      (node (ref "CM") (pin "P$2") (pinfunction "P$2_P$2") (pintype "bidirectional"))
      (node (ref "CR2") (pin "P$1") (pinfunction "P$1_P$1") (pintype "bidirectional"))
      (node (ref "L0") (pin "P$1") (pinfunction "P$1_P$1") (pintype "bidirectional"))
      (node (ref "LM") (pin "P$2") (pinfunction "P$2_P$2") (pintype "bidirectional"))
      (node (ref "LR2") (pin "P$1") (pinfunction "P$1_P$1") (pintype "bidirectional"))
    )
    (net (code "50") (name "Net-(CM2-PadP$2)") (class "Default")
      (node (ref "CM2") (pin "P$2") (pinfunction "P$2_P$2") (pintype "bidirectional"))
      (node (ref "LM") (pin "P$1") (pinfunction "P$1_P$1") (pintype "bidirectional"))
      (node (ref "LM2") (pin "P$2") (pinfunction "P$2_P$2") (pintype "bidirectional"))
    )
    (net (code "51") (name "Net-(CM3-PadP$2)") (class "Default")
      (node (ref "CM3") (pin "P$2") (pinfunction "P$2_P$2") (pintype "bidirectional"))
      (node (ref "LM2") (pin "P$1") (pinfunction "P$1_P$1") (pintype "bidirectional"))
      (node (ref "R2") (pin "P$2") (pinfunction "P$2_P$2") (pintype "bidirectional"))
    )
    (net (code "52") (name "Net-(R2-PadP$1)") (class "Default")
      (node (ref "R2") (pin "P$1") (pinfunction "P$1_P$1") (pintype "bidirectional"))
      (node (ref "RF+") (pin "P$1") (pinfunction "P$1_P$1") (pintype "bidirectional"))
    )
    (net (code "53") (name "Net-(R10-PadP$2)") (class "Default")
      (node (ref "R10") (pin "P$2") (pinfunction "P$2_P$2") (pintype "bidirectional"))
      (node (ref "U$10") (pin "D-") (pinfunction "D-_D-") (pintype "bidirectional"))
    )
    (net (code "54") (name "Net-(R11-PadP$2)") (class "Default")
      (node (ref "R11") (pin "P$2") (pinfunction "P$2_P$2") (pintype "bidirectional"))
      (node (ref "U$10") (pin "D+") (pinfunction "D+_D+") (pintype "bidirectional"))
    )
    (net (code "55") (name "Net-(R12-PadP$1)") (class "Default")
      (node (ref "R12") (pin "P$1") (pinfunction "P$1_P$1") (pintype "bidirectional"))
      (node (ref "U$3") (pin "CATHODE") (pinfunction "CATHODE_CATHODE") (pintype "bidirectional"))
    )
    (net (code "56") (name "Net-(R13-PadP$1)") (class "Default")
      (node (ref "R13") (pin "P$1") (pinfunction "P$1_P$1") (pintype "bidirectional"))
      (node (ref "U$4") (pin "CATHODE") (pinfunction "CATHODE_CATHODE") (pintype "bidirectional"))
    )
    (net (code "57") (name "Net-(RF_IN+-PadP$1)") (class "Default")
      (node (ref "RF_IN+") (pin "P$1") (pinfunction "P$1_P$1") (pintype "bidirectional"))
      (node (ref "U$2") (pin "11_RF_IN") (pinfunction "11_RF_IN_11_RF_IN") (pintype "bidirectional"))
    )
    (net (code "58") (name "Net-(TCXO-OUT)") (class "Default")
      (node (ref "TCXO") (pin "3") (pinfunction "OUT_3") (pintype "bidirectional"))
      (node (ref "U$1") (pin "P17") (pinfunction "XIN_P17") (pintype "bidirectional"))
    )
    (net (code "59") (name "Net-(U$1-NC1)") (class "Default")
      (node (ref "CR1") (pin "P$1") (pinfunction "P$1_P$1") (pintype "bidirectional"))
      (node (ref "LR1") (pin "P$2") (pinfunction "P$2_P$2") (pintype "bidirectional"))
      (node (ref "LR2") (pin "P$2") (pinfunction "P$2_P$2") (pintype "bidirectional"))
      (node (ref "U$1") (pin "P2") (pinfunction "NC1_P2") (pintype "bidirectional"))
    )
    (net (code "60") (name "Net-(U$1-NC2)") (class "Default")
      (node (ref "CR2") (pin "P$2") (pinfunction "P$2_P$2") (pintype "bidirectional"))
      (node (ref "LR1") (pin "P$1") (pinfunction "P$1_P$1") (pintype "bidirectional"))
      (node (ref "U$1") (pin "P3") (pinfunction "NC2_P3") (pintype "bidirectional"))
    )
    (net (code "61") (name "Net-(U$1-TX)") (class "Default")
      (node (ref "C0") (pin "P$2") (pinfunction "P$2_P$2") (pintype "bidirectional"))
      (node (ref "LC") (pin "P$2") (pinfunction "P$2_P$2") (pintype "bidirectional"))
      (node (ref "U$1") (pin "P4") (pinfunction "TX_P4") (pintype "bidirectional"))
    )
    (net (code "62") (name "Net-(U1-AUX)") (class "Default")
      (node (ref "AUX") (pin "P$2") (pinfunction "P$2_P$2") (pintype "bidirectional"))
      (node (ref "U1") (pin "12") (pinfunction "AUX_12") (pintype "bidirectional"))
    )
    (net (code "63") (name "Net-(U1-FB)") (class "Default")
      (node (ref "R3") (pin "P$1") (pinfunction "P$1_P$1") (pintype "bidirectional"))
      (node (ref "R4") (pin "P$2") (pinfunction "P$2_P$2") (pintype "bidirectional"))
      (node (ref "U1") (pin "1") (pinfunction "FB_1") (pintype "bidirectional"))
    )
    (net (code "64") (name "Net-(U1-LDO)") (class "Default")
      (node (ref "LDO") (pin "P$2") (pinfunction "P$2_P$2") (pintype "bidirectional"))
      (node (ref "U1") (pin "2") (pinfunction "LDO_2") (pintype "bidirectional"))
    )
    (net (code "65") (name "Net-(U1-MPPC)") (class "Default")
      (node (ref "R5") (pin "P$2") (pinfunction "P$2_P$2") (pintype "bidirectional"))
      (node (ref "U1") (pin "5") (pinfunction "MPPC_5") (pintype "bidirectional"))
    )
    (net (code "66") (name "Net-(U1-SW)") (class "Default")
      (node (ref "LTC-10UH") (pin "P$1") (pinfunction "P$1_P$1") (pintype "bidirectional"))
      (node (ref "U1") (pin "9") (pinfunction "SW_9") (pintype "bidirectional"))
    )
    (net (code "67") (name "Net-(U2-L1)") (class "Default")
      (node (ref "L1") (pin "P$1") (pinfunction "P$1_P$1") (pintype "bidirectional"))
      (node (ref "U2") (pin "4") (pinfunction "L1_4") (pintype "bidirectional"))
    )
    (net (code "68") (name "Net-(U2-L2)") (class "Default")
      (node (ref "L1") (pin "P$2") (pinfunction "P$2_P$2") (pintype "bidirectional"))
      (node (ref "U2") (pin "2") (pinfunction "L2_2") (pintype "bidirectional"))
    )
    (net (code "69") (name "Net-(U3-RESET_BAR)") (class "Default")
      (node (ref "C9") (pin "P$2") (pinfunction "P$2_P$2") (pintype "bidirectional"))
      (node (ref "R6") (pin "P$2") (pinfunction "P$2_P$2") (pintype "bidirectional"))
      (node (ref "U3") (pin "23") (pinfunction "RESET_BAR_23") (pintype "bidirectional"))
    )
    (net (code "70") (name "unconnected-(ME6211-1.8V-NC-Pad4)") (class "Default")
      (node (ref "ME6211-1.8V") (pin "4") (pinfunction "NC_4") (pintype "bidirectional"))
    )
    (net (code "71") (name "unconnected-(ME6211-2.8V-NC-Pad4)") (class "Default")
      (node (ref "ME6211-2.8V") (pin "4") (pinfunction "NC_4") (pintype "bidirectional"))
    )
    (net (code "72") (name "unconnected-(TCXO-NC-Pad1)") (class "Default")
      (node (ref "TCXO") (pin "1") (pinfunction "NC_1") (pintype "bidirectional"))
    )
    (net (code "73") (name "unconnected-(U$1-GPIO0-PadP9)") (class "Default")
      (node (ref "U$1") (pin "P9") (pinfunction "GPIO0_P9") (pintype "bidirectional"))
    )
    (net (code "74") (name "unconnected-(U$1-GPIO2-PadP19)") (class "Default")
      (node (ref "U$1") (pin "P19") (pinfunction "GPIO2_P19") (pintype "bidirectional"))
    )
    (net (code "75") (name "unconnected-(U$1-GPIO3-PadP20)") (class "Default")
      (node (ref "U$1") (pin "P20") (pinfunction "GPIO3_P20") (pintype "bidirectional"))
    )
    (net (code "76") (name "unconnected-(U$1-NIRQ-PadP11)") (class "Default")
      (node (ref "U$1") (pin "P11") (pinfunction "NIRQ_P11") (pintype "bidirectional"))
    )
    (net (code "77") (name "unconnected-(U$1-TXRAMP-PadP7)") (class "Default")
      (node (ref "U$1") (pin "P7") (pinfunction "TXRAMP_P7") (pintype "bidirectional"))
    )
    (net (code "78") (name "unconnected-(U$1-XOUT-PadP16)") (class "Default")
      (node (ref "U$1") (pin "P16") (pinfunction "XOUT_P16") (pintype "bidirectional"))
    )
    (net (code "79") (name "unconnected-(U$2-Pad4_TIMEPULSE)") (class "Default")
      (node (ref "U$2") (pin "4_TIMEPULSE") (pinfunction "4_TIMEPULSE_4_TIMEPULSE") (pintype "bidirectional"))
    )
    (net (code "80") (name "unconnected-(U$2-Pad5_EXTINT0)") (class "Default")
      (node (ref "U$2") (pin "5_EXTINT0") (pinfunction "5_EXTINT0_5_EXTINT0") (pintype "bidirectional"))
    )
    (net (code "81") (name "unconnected-(U$2-Pad13_ANTON)") (class "Default")
      (node (ref "U$2") (pin "13_ANTON") (pinfunction "13_ANTON_13_ANTON") (pintype "bidirectional"))
    )
    (net (code "82") (name "unconnected-(U$2-Pad14_VCC_RF)") (class "Default")
      (node (ref "U$2") (pin "14_VCC_RF") (pinfunction "14_VCC_RF_14_VCC_RF") (pintype "bidirectional"))
    )
    (net (code "83") (name "unconnected-(U$2-Pad15_RESERVED)") (class "Default")
      (node (ref "U$2") (pin "15_RESERVED") (pinfunction "15_RESERVED_15_RESERVED") (pintype "bidirectional"))
    )
    (net (code "84") (name "unconnected-(U$2-Pad16_SDA2)") (class "Default")
      (node (ref "U$2") (pin "16_SDA2") (pinfunction "16_SDA2_16_SDA2") (pintype "bidirectional"))
    )
    (net (code "85") (name "unconnected-(U$2-Pad17_SCL2)") (class "Default")
      (node (ref "U$2") (pin "17_SCL2") (pinfunction "17_SCL2_17_SCL2") (pintype "bidirectional"))
    )
    (net (code "86") (name "unconnected-(U$2-Pad18_RESERVED)") (class "Default")
      (node (ref "U$2") (pin "18_RESERVED") (pinfunction "18_RESERVED_18_RESERVED") (pintype "bidirectional"))
    )
    (net (code "87") (name "unconnected-(U$10-PadID)") (class "Default")
      (node (ref "U$10") (pin "ID") (pinfunction "ID_ID") (pintype "bidirectional"))
    )
    (net (code "88") (name "unconnected-(U1-PGOOD-Pad10)") (class "Default")
      (node (ref "U1") (pin "10") (pinfunction "PGOOD_10") (pintype "bidirectional"))
    )
    (net (code "89") (name "unconnected-(U1-~{SHDN}-Pad4)") (class "Default")
      (node (ref "U1") (pin "4") (pinfunction "~{SHDN}_4") (pintype "bidirectional"))
    )
    (net (code "90") (name "unconnected-(U3-FLASH-Pad30)") (class "Default")
      (node (ref "U3") (pin "30") (pinfunction "FLASH_30") (pintype "bidirectional"))
    )
    (net (code "91") (name "unconnected-(U3-GPIO10-Pad13)") (class "Default")
      (node (ref "U3") (pin "13") (pinfunction "GPIO10_13") (pintype "bidirectional"))
    )
    (net (code "92") (name "unconnected-(U3-NC1-Pad2)") (class "Default")
      (node (ref "U3") (pin "2") (pinfunction "NC1_2") (pintype "bidirectional"))
    )
    (net (code "93") (name "unconnected-(U3-NC2-Pad3)") (class "Default")
      (node (ref "U3") (pin "3") (pinfunction "NC2_3") (pintype "bidirectional"))
    )
    (net (code "94") (name "unconnected-(U3-NC3-Pad12)") (class "Default")
      (node (ref "U3") (pin "12") (pinfunction "NC3_12") (pintype "bidirectional"))
    )
    (net (code "95") (name "unconnected-(U3-NC4-Pad14)") (class "Default")
      (node (ref "U3") (pin "14") (pinfunction "NC4_14") (pintype "bidirectional"))
    )
    (net (code "96") (name "unconnected-(U3-NC5-Pad19)") (class "Default")
      (node (ref "U3") (pin "19") (pinfunction "NC5_19") (pintype "bidirectional"))
    )
    (net (code "97") (name "unconnected-(U3-NC6-Pad20)") (class "Default")
      (node (ref "U3") (pin "20") (pinfunction "NC6_20") (pintype "bidirectional"))
    )
    (net (code "98") (name "unconnected-(U4-ADVREF-Pad1)") (class "Default")
      (node (ref "U4") (pin "1") (pinfunction "ADVREF_1") (pintype "bidirectional"))
    )
    (net (code "99") (name "unconnected-(U4-PA2-Pad44)") (class "Default")
      (node (ref "U4") (pin "44") (pinfunction "PA2_44") (pintype "bidirectional"))
    )
    (net (code "100") (name "unconnected-(U4-PA17-Pad9)") (class "Default")
      (node (ref "U4") (pin "9") (pinfunction "PA17_9") (pintype "bidirectional"))
    )
    (net (code "101") (name "unconnected-(U4-PA18-Pad10)") (class "Default")
      (node (ref "U4") (pin "10") (pinfunction "PA18_10") (pintype "bidirectional"))
    )
    (net (code "102") (name "unconnected-(U4-PA19-Pad13)") (class "Default")
      (node (ref "U4") (pin "13") (pinfunction "PA19_13") (pintype "bidirectional"))
    )
    (net (code "103") (name "unconnected-(U4-PA21-Pad11)") (class "Default")
      (node (ref "U4") (pin "11") (pinfunction "PA21_11") (pintype "bidirectional"))
    )
    (net (code "104") (name "unconnected-(U4-PB0-Pad3)") (class "Default")
      (node (ref "U4") (pin "3") (pinfunction "PB0_3") (pintype "bidirectional"))
    )
    (net (code "105") (name "unconnected-(U4-PB1-Pad4)") (class "Default")
      (node (ref "U4") (pin "4") (pinfunction "PB1_4") (pintype "bidirectional"))
    )
    (net (code "106") (name "unconnected-(U4-PB6-Pad51)") (class "Default")
      (node (ref "U4") (pin "51") (pinfunction "PB6_51") (pintype "bidirectional"))
    )
    (net (code "107") (name "unconnected-(U4-PB7-Pad53)") (class "Default")
      (node (ref "U4") (pin "53") (pinfunction "PB7_53") (pintype "bidirectional"))
    )
    (net (code "108") (name "unconnected-(U4-PB14-Pad63)") (class "Default")
      (node (ref "U4") (pin "63") (pinfunction "PB14_63") (pintype "bidirectional"))
    )
    (net (code "109") (name "unconnected-(U4-TST-Pad40)") (class "Default")
      (node (ref "U4") (pin "40") (pinfunction "TST_40") (pintype "bidirectional"))
    )
  )
)
